# FabEEG_v6.net
KiCad netlist of a schematic drawn in EAGLE
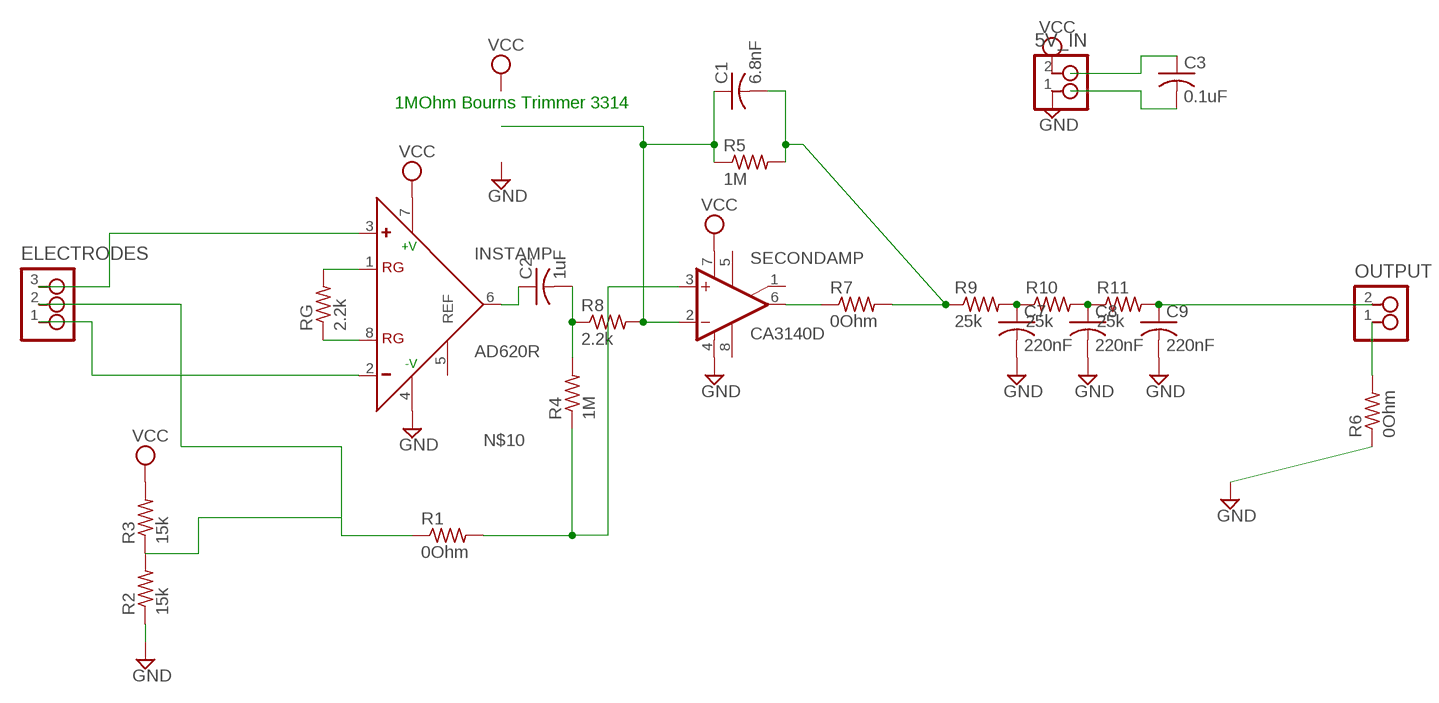
[diagram p0: schematic, sheet 1]

(export (version "E")
  (design (tool "Eeschema 10.0.6"))
  (components
    (comp (ref "5V_IN")
      (value "2_PIN_HEADERHEADER")
      (footprint "eagle-import:SMT_PINS_2")
      (libsource (lib "eagle-import") (part "2_PIN_HEADERHEADER"))
    )
    (comp (ref "C1")
      (value "6.8nF")
      (footprint "eagle-import:C1206")
      (libsource (lib "eagle-import") (part "C-USC1206"))
    )
    (comp (ref "C2")
      (value "1uF")
      (footprint "eagle-import:C1206")
      (libsource (lib "eagle-import") (part "C-USC1206"))
    )
    (comp (ref "C3")
      (value "0.1uF")
      (footprint "eagle-import:C1206")
      (libsource (lib "eagle-import") (part "resistor_C-USC1206"))
    )
    (comp (ref "C7")
      (value "220nF")
      (footprint "eagle-import:C1206")
      (libsource (lib "eagle-import") (part "C-USC1206"))
    )
    (comp (ref "C8")
      (value "220nF")
      (footprint "eagle-import:C1206")
      (libsource (lib "eagle-import") (part "C-USC1206"))
    )
    (comp (ref "C9")
      (value "220nF")
      (footprint "eagle-import:C1206")
      (libsource (lib "eagle-import") (part "C-USC1206"))
    )
    (comp (ref "ELECTRODES")
      (value "3_PIN_HEADERHEADER")
      (footprint "eagle-import:SMT_PINS_3")
      (libsource (lib "eagle-import") (part "3_PIN_HEADERHEADER"))
    )
    (comp (ref "INSTAMP")
      (value "AD620R")
      (footprint "eagle-import:SO8")
      (libsource (lib "eagle-import") (part "AD620R"))
    )
    (comp (ref "OUTPUT")
      (value "2_PIN_HEADERHEADER")
      (footprint "eagle-import:SMT_PINS_2")
      (libsource (lib "eagle-import") (part "2_PIN_HEADERHEADER"))
    )
    (comp (ref "R1")
      (value "0Ohm")
      (footprint "eagle-import:R1206")
      (libsource (lib "eagle-import") (part "R-US_R1206"))
    )
    (comp (ref "R2")
      (value "15k")
      (footprint "eagle-import:R1206")
      (libsource (lib "eagle-import") (part "R-US_R1206"))
    )
    (comp (ref "R3")
      (value "15k")
      (footprint "eagle-import:R1206")
      (libsource (lib "eagle-import") (part "R-US_R1206"))
    )
    (comp (ref "R4")
      (value "1M")
      (footprint "eagle-import:R1206")
      (libsource (lib "eagle-import") (part "R-US_R1206"))
    )
    (comp (ref "R5")
      (value "1M")
      (footprint "eagle-import:R1206")
      (libsource (lib "eagle-import") (part "R-US_R1206"))
    )
    (comp (ref "R6")
      (value "0Ohm")
      (footprint "eagle-import:R1206")
      (libsource (lib "eagle-import") (part "R-US_R1206"))
    )
    (comp (ref "R7")
      (value "0Ohm")
      (footprint "eagle-import:R1206")
      (libsource (lib "eagle-import") (part "R-US_R1206"))
    )
    (comp (ref "R8")
      (value "2.2k")
      (footprint "eagle-import:R1206")
      (libsource (lib "eagle-import") (part "R-US_R1206"))
    )
    (comp (ref "R9")
      (value "25k")
      (footprint "eagle-import:R1206")
      (libsource (lib "eagle-import") (part "R-US_R1206"))
    )
    (comp (ref "R10")
      (value "25k")
      (footprint "eagle-import:R1206")
      (libsource (lib "eagle-import") (part "R-US_R1206"))
    )
    (comp (ref "R11")
      (value "25k")
      (footprint "eagle-import:R1206")
      (libsource (lib "eagle-import") (part "R-US_R1206"))
    )
    (comp (ref "RG")
      (value "2.2k")
      (footprint "eagle-import:R1206")
      (libsource (lib "eagle-import") (part "R-US_R1206"))
    )
    (comp (ref "SECONDAMP")
      (value "CA3140D")
      (footprint "eagle-import:SO08")
      (libsource (lib "eagle-import") (part "CA3140D"))
    )
  )
  (nets
    (net (code "1") (name "/N$10") (class "Default")
      (node (ref "R1") (pin "2") (pinfunction "2_2") (pintype "passive"))
      (node (ref "R4") (pin "1") (pinfunction "1_1") (pintype "passive"))
      (node (ref "SECONDAMP") (pin "3") (pinfunction "+IN_3") (pintype "input"))
    )
    (net (code "2") (name "GND") (class "Default")
      (node (ref "5V_IN") (pin "1") (pinfunction "1_1") (pintype "bidirectional"))
      (node (ref "C7") (pin "2") (pinfunction "2_2") (pintype "passive"))
      (node (ref "C8") (pin "2") (pinfunction "2_2") (pintype "passive"))
      (node (ref "C9") (pin "2") (pinfunction "2_2") (pintype "passive"))
      (node (ref "INSTAMP") (pin "4") (pinfunction "-V_4") (pintype "power_in"))
      (node (ref "R2") (pin "1") (pinfunction "1_1") (pintype "passive"))
      (node (ref "R6") (pin "1") (pinfunction "1_1") (pintype "passive"))
      (node (ref "SECONDAMP") (pin "4") (pinfunction "V-_4") (pintype "power_in"))
    )
    (net (code "3") (name "Net-(C1-Pad2)") (class "Default")
      (node (ref "C1") (pin "2") (pinfunction "2_2") (pintype "passive"))
      (node (ref "R5") (pin "2") (pinfunction "2_2") (pintype "passive"))
      (node (ref "R7") (pin "2") (pinfunction "2_2") (pintype "passive"))
      (node (ref "R9") (pin "1") (pinfunction "1_1") (pintype "passive"))
    )
    (net (code "4") (name "Net-(C2-Pad2)") (class "Default")
      (node (ref "C2") (pin "2") (pinfunction "2_2") (pintype "passive"))
      (node (ref "R4") (pin "2") (pinfunction "2_2") (pintype "passive"))
      (node (ref "R8") (pin "1") (pinfunction "1_1") (pintype "passive"))
    )
    (net (code "5") (name "Net-(C7-Pad1)") (class "Default")
      (node (ref "C7") (pin "1") (pinfunction "1_1") (pintype "passive"))
      (node (ref "R10") (pin "1") (pinfunction "1_1") (pintype "passive"))
      (node (ref "R9") (pin "2") (pinfunction "2_2") (pintype "passive"))
    )
    (net (code "6") (name "Net-(C8-Pad1)") (class "Default")
      (node (ref "C8") (pin "1") (pinfunction "1_1") (pintype "passive"))
      (node (ref "R10") (pin "2") (pinfunction "2_2") (pintype "passive"))
      (node (ref "R11") (pin "1") (pinfunction "1_1") (pintype "passive"))
    )
    (net (code "7") (name "Net-(C9-Pad1)") (class "Default")
      (node (ref "C9") (pin "1") (pinfunction "1_1") (pintype "passive"))
      (node (ref "OUTPUT") (pin "2") (pinfunction "2_2") (pintype "bidirectional"))
      (node (ref "R11") (pin "2") (pinfunction "2_2") (pintype "passive"))
    )
    (net (code "8") (name "Net-(ELECTRODES-P$1)") (class "Default")
      (node (ref "ELECTRODES") (pin "1") (pinfunction "P$1_1") (pintype "bidirectional"))
      (node (ref "INSTAMP") (pin "2") (pinfunction "-_2") (pintype "input"))
    )
    (net (code "9") (name "Net-(ELECTRODES-P$2)") (class "Default")
      (node (ref "ELECTRODES") (pin "2") (pinfunction "P$2_2") (pintype "bidirectional"))
      (node (ref "R1") (pin "1") (pinfunction "1_1") (pintype "passive"))
      (node (ref "R2") (pin "2") (pinfunction "2_2") (pintype "passive"))
      (node (ref "R3") (pin "1") (pinfunction "1_1") (pintype "passive"))
    )
    (net (code "10") (name "Net-(ELECTRODES-P$3)") (class "Default")
      (node (ref "ELECTRODES") (pin "3") (pinfunction "P$3_3") (pintype "bidirectional"))
      (node (ref "INSTAMP") (pin "3") (pinfunction "+_3") (pintype "input"))
    )
    (net (code "11") (name "Net-(INSTAMP-OUT)") (class "Default")
      (node (ref "C2") (pin "1") (pinfunction "1_1") (pintype "passive"))
      (node (ref "INSTAMP") (pin "6") (pinfunction "OUT_6") (pintype "output"))
    )
    (net (code "12") (name "Net-(INSTAMP-RG-Pad1)") (class "Default")
      (node (ref "INSTAMP") (pin "1") (pinfunction "RG_1") (pintype "passive"))
      (node (ref "RG") (pin "2") (pinfunction "2_2") (pintype "passive"))
    )
    (net (code "13") (name "Net-(INSTAMP-RG-Pad8)") (class "Default")
      (node (ref "INSTAMP") (pin "8") (pinfunction "RG_8") (pintype "passive"))
      (node (ref "RG") (pin "1") (pinfunction "1_1") (pintype "passive"))
    )
    (net (code "14") (name "Net-(OUTPUT-Pad1)") (class "Default")
      (node (ref "OUTPUT") (pin "1") (pinfunction "1_1") (pintype "bidirectional"))
      (node (ref "R6") (pin "2") (pinfunction "2_2") (pintype "passive"))
    )
    (net (code "15") (name "Net-(SECONDAMP--IN)") (class "Default")
      (node (ref "C1") (pin "1") (pinfunction "1_1") (pintype "passive"))
      (node (ref "R5") (pin "1") (pinfunction "1_1") (pintype "passive"))
      (node (ref "R8") (pin "2") (pinfunction "2_2") (pintype "passive"))
      (node (ref "SECONDAMP") (pin "2") (pinfunction "-IN_2") (pintype "input"))
    )
    (net (code "16") (name "Net-(SECONDAMP-OUT)") (class "Default")
      (node (ref "R7") (pin "1") (pinfunction "1_1") (pintype "passive"))
      (node (ref "SECONDAMP") (pin "6") (pinfunction "OUT_6") (pintype "output"))
    )
    (net (code "17") (name "VCC") (class "Default")
      (node (ref "5V_IN") (pin "2") (pinfunction "2_2") (pintype "bidirectional"))
      (node (ref "INSTAMP") (pin "7") (pinfunction "+V_7") (pintype "power_in"))
      (node (ref "R3") (pin "2") (pinfunction "2_2") (pintype "passive"))
      (node (ref "SECONDAMP") (pin "7") (pinfunction "V+_7") (pintype "power_in"))
    )
    (net (code "18") (name "unconnected-(C3-Pad1)") (class "Default")
      (node (ref "C3") (pin "1") (pinfunction "1_1") (pintype "passive"))
    )
    (net (code "19") (name "unconnected-(C3-Pad2)") (class "Default")
      (node (ref "C3") (pin "2") (pinfunction "2_2") (pintype "passive"))
    )
    (net (code "20") (name "unconnected-(INSTAMP-REF-Pad5)") (class "Default")
      (node (ref "INSTAMP") (pin "5") (pinfunction "REF_5") (pintype "passive"))
    )
    (net (code "21") (name "unconnected-(SECONDAMP-CMP-Pad8)") (class "Default")
      (node (ref "SECONDAMP") (pin "8") (pinfunction "CMP_8") (pintype "passive"))
    )
    (net (code "22") (name "unconnected-(SECONDAMP-ON-Pad5)") (class "Default")
      (node (ref "SECONDAMP") (pin "5") (pinfunction "ON_5") (pintype "passive"))
    )
    (net (code "23") (name "unconnected-(SECONDAMP-ON{slash}CMP-Pad1)") (class "Default")
      (node (ref "SECONDAMP") (pin "1") (pinfunction "ON/CMP_1") (pintype "passive"))
    )
  )
)
